# ADC.net
KiCad netlist of a schematic drawn in Altium Designer
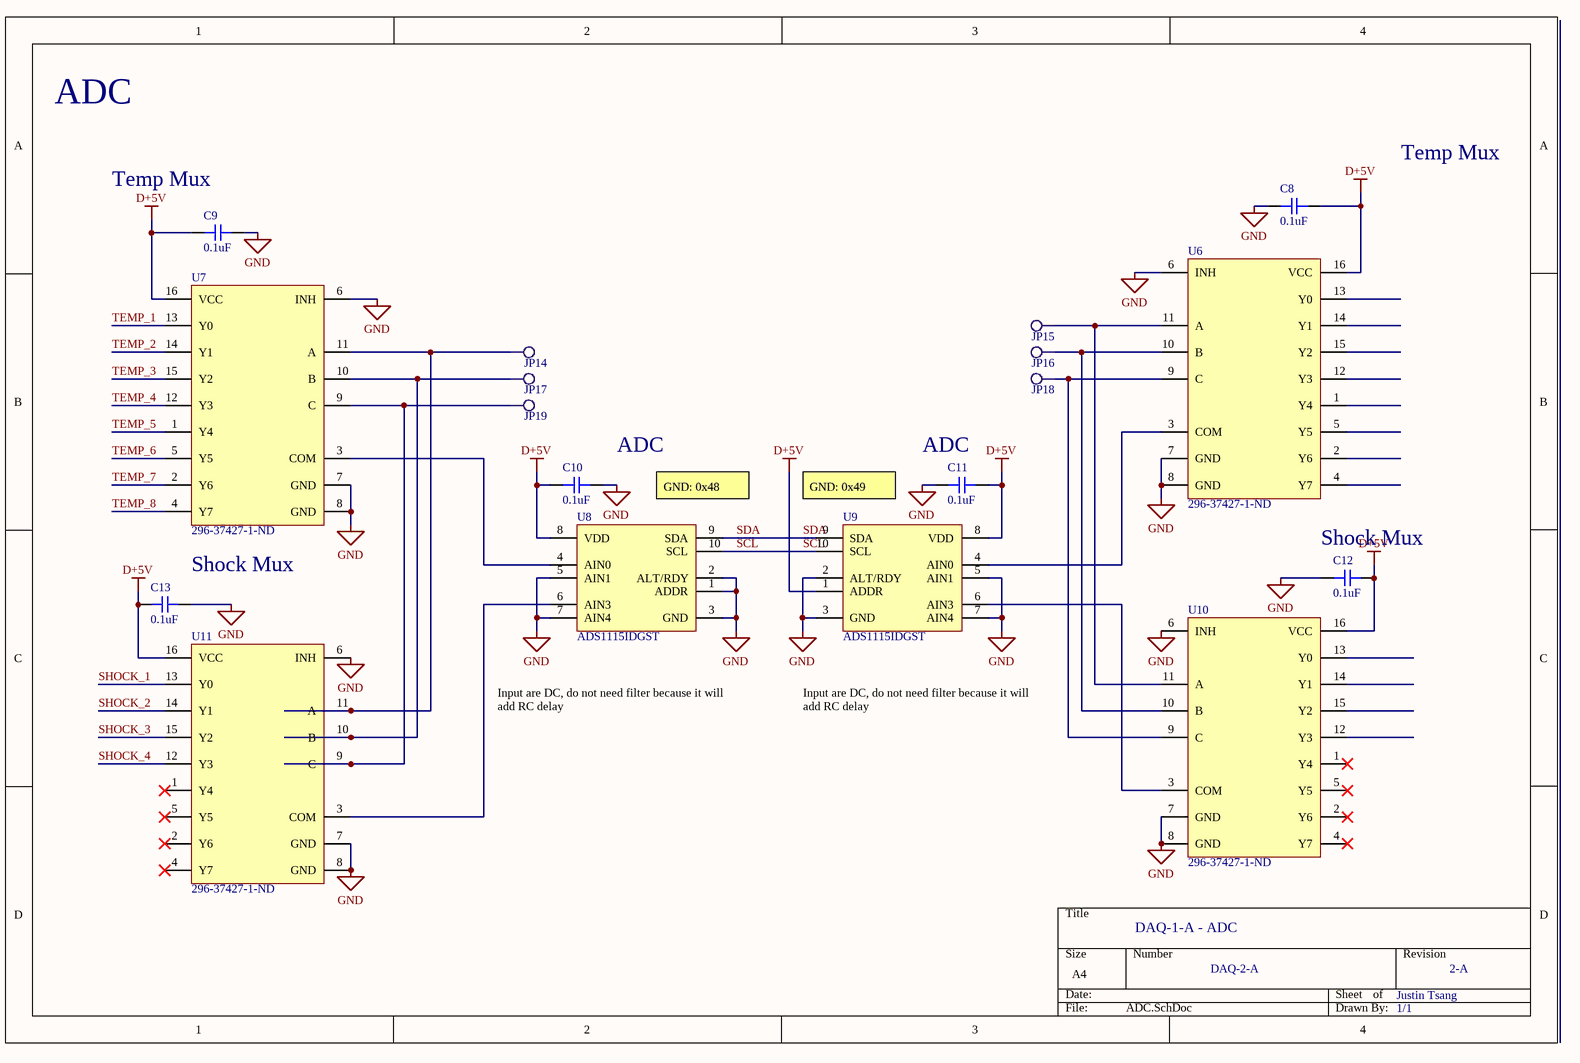
[diagram p0: ADC.SchDoc]

(export (version "E")
  (design (tool "Eeschema 10.0.6"))
  (components
    (comp (ref "C8")
      (value "0.1uF")
      (footprint "CAP-0603")
      (description "CAP CER 0.1UF 16V X7R 0603")
      (fields
        (field (name "MANUFACTURER") "KEMET")
        (field (name "MANUFACTURER PART NUMBER") "C0603C104M4RACTU")
      )
      (libsource (lib "Capacitors") (part "0603-0.1uF-16V"))
    )
    (comp (ref "C9")
      (value "0.1uF")
      (footprint "CAP-0603")
      (description "CAP CER 0.1UF 16V X7R 0603")
      (fields
        (field (name "MANUFACTURER") "KEMET")
        (field (name "MANUFACTURER PART NUMBER") "C0603C104M4RACTU")
      )
      (libsource (lib "Capacitors") (part "0603-0.1uF-16V"))
    )
    (comp (ref "C10")
      (value "0.1uF")
      (footprint "CAP-0603")
      (description "CAP CER 0.1UF 16V X7R 0603")
      (fields
        (field (name "MANUFACTURER") "KEMET")
        (field (name "MANUFACTURER PART NUMBER") "C0603C104M4RACTU")
      )
      (libsource (lib "Capacitors") (part "0603-0.1uF-16V"))
    )
    (comp (ref "C11")
      (value "0.1uF")
      (footprint "CAP-0603")
      (description "CAP CER 0.1UF 16V X7R 0603")
      (fields
        (field (name "MANUFACTURER") "KEMET")
        (field (name "MANUFACTURER PART NUMBER") "C0603C104M4RACTU")
      )
      (libsource (lib "Capacitors") (part "0603-0.1uF-16V"))
    )
    (comp (ref "C12")
      (value "0.1uF")
      (footprint "CAP-0603")
      (description "CAP CER 0.1UF 16V X7R 0603")
      (fields
        (field (name "MANUFACTURER") "KEMET")
        (field (name "MANUFACTURER PART NUMBER") "C0603C104M4RACTU")
      )
      (libsource (lib "Capacitors") (part "0603-0.1uF-16V"))
    )
    (comp (ref "C13")
      (value "0.1uF")
      (footprint "CAP-0603")
      (description "CAP CER 0.1UF 16V X7R 0603")
      (fields
        (field (name "MANUFACTURER") "KEMET")
        (field (name "MANUFACTURER PART NUMBER") "C0603C104M4RACTU")
      )
      (libsource (lib "Capacitors") (part "0603-0.1uF-16V"))
    )
    (comp (ref "JP14")
      (value "Testpoint2")
      (footprint "TP2")
      (description "Single layer pad TP")
      (libsource (lib "Misc") (part "Testpoint2"))
    )
    (comp (ref "JP15")
      (value "Testpoint2")
      (footprint "TP2")
      (description "Single layer pad TP")
      (libsource (lib "Misc") (part "Testpoint2"))
    )
    (comp (ref "JP16")
      (value "Testpoint2")
      (footprint "TP2")
      (description "Single layer pad TP")
      (libsource (lib "Misc") (part "Testpoint2"))
    )
    (comp (ref "JP17")
      (value "Testpoint2")
      (footprint "TP2")
      (description "Single layer pad TP")
      (libsource (lib "Misc") (part "Testpoint2"))
    )
    (comp (ref "JP18")
      (value "Testpoint2")
      (footprint "TP2")
      (description "Single layer pad TP")
      (libsource (lib "Misc") (part "Testpoint2"))
    )
    (comp (ref "JP19")
      (value "Testpoint2")
      (footprint "TP2")
      (description "Single layer pad TP")
      (libsource (lib "Misc") (part "Testpoint2"))
    )
    (comp (ref "U6")
      (value "296-37427-1-ND")
      (footprint "16-SOIC")
      (description "IC MUX/DEMUX 8X1 16SOIC")
      (fields
        (field (name "MANUFACTURER") "Texas Instruments")
        (field (name "MANUFACTURER PART NUMBER") "SN74LV4051ATDWRQ1")
      )
      (libsource (lib "ICs") (part "MUX-SN74LV4051ATDWRQ1"))
    )
    (comp (ref "U7")
      (value "296-37427-1-ND")
      (footprint "16-SOIC")
      (description "IC MUX/DEMUX 8X1 16SOIC")
      (fields
        (field (name "MANUFACTURER") "Texas Instruments")
        (field (name "MANUFACTURER PART NUMBER") "SN74LV4051ATDWRQ1")
      )
      (libsource (lib "") (part "MUX-SN74LV4051ATDWRQ1_1"))
    )
    (comp (ref "U8")
      (value "ADS1115IDGST")
      (footprint "VSSOP50P310X310-10P")
      (fields (field (name "MANUFACTURER") "Texas Instruments"))
      (libsource (lib "") (part "IC_ADS1115_1"))
    )
    (comp (ref "U9")
      (value "ADS1115IDGST")
      (footprint "VSSOP50P310X310-10P")
      (fields (field (name "MANUFACTURER") "Texas Instruments"))
      (libsource (lib "New_Parts") (part "IC_ADS1115"))
    )
    (comp (ref "U10")
      (value "296-37427-1-ND")
      (footprint "16-SOIC")
      (description "IC MUX/DEMUX 8X1 16SOIC")
      (fields
        (field (name "MANUFACTURER") "Texas Instruments")
        (field (name "MANUFACTURER PART NUMBER") "SN74LV4051ATDWRQ1")
      )
      (libsource (lib "ICs") (part "MUX-SN74LV4051ATDWRQ1"))
    )
    (comp (ref "U11")
      (value "296-37427-1-ND")
      (footprint "16-SOIC")
      (description "IC MUX/DEMUX 8X1 16SOIC")
      (fields
        (field (name "MANUFACTURER") "Texas Instruments")
        (field (name "MANUFACTURER PART NUMBER") "SN74LV4051ATDWRQ1")
      )
      (libsource (lib "") (part "MUX-SN74LV4051ATDWRQ1_1"))
    )
  )
  (nets
    (net (code "1") (name "/SCL") (class "Default")
      (node (ref "U8") (pin "10") (pinfunction "SCL_10") (pintype "passive"))
      (node (ref "U9") (pin "10") (pinfunction "SCL_10") (pintype "passive"))
    )
    (net (code "2") (name "/SDA") (class "Default")
      (node (ref "U8") (pin "9") (pinfunction "SDA_9") (pintype "passive"))
      (node (ref "U9") (pin "9") (pinfunction "SDA_9") (pintype "passive"))
    )
    (net (code "3") (name "/SHOCK_1") (class "Default")
      (node (ref "U11") (pin "13") (pinfunction "Y0_13") (pintype "passive"))
    )
    (net (code "4") (name "/SHOCK_2") (class "Default")
      (node (ref "U11") (pin "14") (pinfunction "Y1_14") (pintype "passive"))
    )
    (net (code "5") (name "/SHOCK_3") (class "Default")
      (node (ref "U11") (pin "15") (pinfunction "Y2_15") (pintype "passive"))
    )
    (net (code "6") (name "/SHOCK_4") (class "Default")
      (node (ref "U11") (pin "12") (pinfunction "Y3_12") (pintype "passive"))
    )
    (net (code "7") (name "/TEMP_1") (class "Default")
      (node (ref "U7") (pin "13") (pinfunction "Y0_13") (pintype "passive"))
    )
    (net (code "8") (name "/TEMP_2") (class "Default")
      (node (ref "U7") (pin "14") (pinfunction "Y1_14") (pintype "passive"))
    )
    (net (code "9") (name "/TEMP_3") (class "Default")
      (node (ref "U7") (pin "15") (pinfunction "Y2_15") (pintype "passive"))
    )
    (net (code "10") (name "/TEMP_4") (class "Default")
      (node (ref "U7") (pin "12") (pinfunction "Y3_12") (pintype "passive"))
    )
    (net (code "11") (name "/TEMP_5") (class "Default")
      (node (ref "U7") (pin "1") (pinfunction "Y4_1") (pintype "passive"))
    )
    (net (code "12") (name "/TEMP_6") (class "Default")
      (node (ref "U7") (pin "5") (pinfunction "Y5_5") (pintype "passive"))
    )
    (net (code "13") (name "/TEMP_7") (class "Default")
      (node (ref "U7") (pin "2") (pinfunction "Y6_2") (pintype "passive"))
    )
    (net (code "14") (name "/TEMP_8") (class "Default")
      (node (ref "U7") (pin "4") (pinfunction "Y7_4") (pintype "passive"))
    )
    (net (code "15") (name "D+5V") (class "Default")
      (node (ref "C10") (pin "2") (pinfunction "2_2") (pintype "passive"))
      (node (ref "C11") (pin "2") (pinfunction "2_2") (pintype "passive"))
      (node (ref "C12") (pin "2") (pinfunction "2_2") (pintype "passive"))
      (node (ref "C13") (pin "2") (pinfunction "2_2") (pintype "passive"))
      (node (ref "C8") (pin "2") (pinfunction "2_2") (pintype "passive"))
      (node (ref "C9") (pin "2") (pinfunction "2_2") (pintype "passive"))
      (node (ref "U10") (pin "16") (pinfunction "VCC_16") (pintype "passive"))
      (node (ref "U11") (pin "16") (pinfunction "VCC_16") (pintype "passive"))
      (node (ref "U6") (pin "16") (pinfunction "VCC_16") (pintype "passive"))
      (node (ref "U7") (pin "16") (pinfunction "VCC_16") (pintype "passive"))
      (node (ref "U8") (pin "8") (pinfunction "VDD_8") (pintype "passive"))
      (node (ref "U9") (pin "1") (pinfunction "ADDR_1") (pintype "passive"))
      (node (ref "U9") (pin "8") (pinfunction "VDD_8") (pintype "passive"))
    )
    (net (code "16") (name "GND") (class "Default")
      (node (ref "C10") (pin "1") (pinfunction "1_1") (pintype "passive"))
      (node (ref "C11") (pin "1") (pinfunction "1_1") (pintype "passive"))
      (node (ref "C12") (pin "1") (pinfunction "1_1") (pintype "passive"))
      (node (ref "C13") (pin "1") (pinfunction "1_1") (pintype "passive"))
      (node (ref "C8") (pin "1") (pinfunction "1_1") (pintype "passive"))
      (node (ref "C9") (pin "1") (pinfunction "1_1") (pintype "passive"))
      (node (ref "U10") (pin "6") (pinfunction "INH_6") (pintype "passive"))
      (node (ref "U10") (pin "7") (pinfunction "GND_7") (pintype "passive"))
      (node (ref "U10") (pin "8") (pinfunction "GND_8") (pintype "passive"))
      (node (ref "U11") (pin "6") (pinfunction "INH_6") (pintype "passive"))
      (node (ref "U11") (pin "7") (pinfunction "GND_7") (pintype "passive"))
      (node (ref "U11") (pin "8") (pinfunction "GND_8") (pintype "passive"))
      (node (ref "U6") (pin "6") (pinfunction "INH_6") (pintype "passive"))
      (node (ref "U6") (pin "7") (pinfunction "GND_7") (pintype "passive"))
      (node (ref "U6") (pin "8") (pinfunction "GND_8") (pintype "passive"))
      (node (ref "U7") (pin "6") (pinfunction "INH_6") (pintype "passive"))
      (node (ref "U7") (pin "7") (pinfunction "GND_7") (pintype "passive"))
      (node (ref "U7") (pin "8") (pinfunction "GND_8") (pintype "passive"))
      (node (ref "U8") (pin "1") (pinfunction "ADDR_1") (pintype "passive"))
      (node (ref "U8") (pin "2") (pinfunction "ALT/RDY_2") (pintype "passive"))
      (node (ref "U8") (pin "3") (pinfunction "GND_3") (pintype "passive"))
      (node (ref "U8") (pin "5") (pinfunction "AIN1_5") (pintype "passive"))
      (node (ref "U8") (pin "7") (pinfunction "AIN4_7") (pintype "passive"))
      (node (ref "U9") (pin "2") (pinfunction "ALT/RDY_2") (pintype "passive"))
      (node (ref "U9") (pin "3") (pinfunction "GND_3") (pintype "passive"))
      (node (ref "U9") (pin "5") (pinfunction "AIN1_5") (pintype "passive"))
      (node (ref "U9") (pin "7") (pinfunction "AIN4_7") (pintype "passive"))
    )
    (net (code "17") (name "Net-(U6-COM)") (class "Default")
      (node (ref "U6") (pin "3") (pinfunction "COM_3") (pintype "passive"))
      (node (ref "U9") (pin "4") (pinfunction "AIN0_4") (pintype "passive"))
    )
    (net (code "18") (name "Net-(U7-COM)") (class "Default")
      (node (ref "U7") (pin "3") (pinfunction "COM_3") (pintype "passive"))
      (node (ref "U8") (pin "4") (pinfunction "AIN0_4") (pintype "passive"))
    )
    (net (code "19") (name "Net-(U10-A)") (class "Default")
      (node (ref "JP15") (pin "1") (pinfunction "1_1") (pintype "passive"))
      (node (ref "U10") (pin "11") (pinfunction "A_11") (pintype "passive"))
      (node (ref "U6") (pin "11") (pinfunction "A_11") (pintype "passive"))
    )
    (net (code "20") (name "Net-(U10-B)") (class "Default")
      (node (ref "JP16") (pin "1") (pinfunction "1_1") (pintype "passive"))
      (node (ref "U10") (pin "10") (pinfunction "B_10") (pintype "passive"))
      (node (ref "U6") (pin "10") (pinfunction "B_10") (pintype "passive"))
    )
    (net (code "21") (name "Net-(U10-C)") (class "Default")
      (node (ref "JP18") (pin "1") (pinfunction "1_1") (pintype "passive"))
      (node (ref "U10") (pin "9") (pinfunction "C_9") (pintype "passive"))
      (node (ref "U6") (pin "9") (pinfunction "C_9") (pintype "passive"))
    )
    (net (code "22") (name "Net-(U10-COM)") (class "Default")
      (node (ref "U10") (pin "3") (pinfunction "COM_3") (pintype "passive"))
      (node (ref "U9") (pin "6") (pinfunction "AIN3_6") (pintype "passive"))
    )
    (net (code "23") (name "Net-(U11-A)") (class "Default")
      (node (ref "JP14") (pin "1") (pinfunction "1_1") (pintype "passive"))
      (node (ref "U11") (pin "11") (pinfunction "A_11") (pintype "passive"))
      (node (ref "U7") (pin "11") (pinfunction "A_11") (pintype "passive"))
    )
    (net (code "24") (name "Net-(U11-B)") (class "Default")
      (node (ref "JP17") (pin "1") (pinfunction "1_1") (pintype "passive"))
      (node (ref "U11") (pin "10") (pinfunction "B_10") (pintype "passive"))
      (node (ref "U7") (pin "10") (pinfunction "B_10") (pintype "passive"))
    )
    (net (code "25") (name "Net-(U11-C)") (class "Default")
      (node (ref "JP19") (pin "1") (pinfunction "1_1") (pintype "passive"))
      (node (ref "U11") (pin "9") (pinfunction "C_9") (pintype "passive"))
      (node (ref "U7") (pin "9") (pinfunction "C_9") (pintype "passive"))
    )
    (net (code "26") (name "Net-(U11-COM)") (class "Default")
      (node (ref "U11") (pin "3") (pinfunction "COM_3") (pintype "passive"))
      (node (ref "U8") (pin "6") (pinfunction "AIN3_6") (pintype "passive"))
    )
    (net (code "27") (name "unconnected-(U6-Y0-Pad13)") (class "Default")
      (node (ref "U6") (pin "13") (pinfunction "Y0_13") (pintype "passive"))
    )
    (net (code "28") (name "unconnected-(U6-Y1-Pad14)") (class "Default")
      (node (ref "U6") (pin "14") (pinfunction "Y1_14") (pintype "passive"))
    )
    (net (code "29") (name "unconnected-(U6-Y2-Pad15)") (class "Default")
      (node (ref "U6") (pin "15") (pinfunction "Y2_15") (pintype "passive"))
    )
    (net (code "30") (name "unconnected-(U6-Y3-Pad12)") (class "Default")
      (node (ref "U6") (pin "12") (pinfunction "Y3_12") (pintype "passive"))
    )
    (net (code "31") (name "unconnected-(U6-Y4-Pad1)") (class "Default")
      (node (ref "U6") (pin "1") (pinfunction "Y4_1") (pintype "passive"))
    )
    (net (code "32") (name "unconnected-(U6-Y5-Pad5)") (class "Default")
      (node (ref "U6") (pin "5") (pinfunction "Y5_5") (pintype "passive"))
    )
    (net (code "33") (name "unconnected-(U6-Y6-Pad2)") (class "Default")
      (node (ref "U6") (pin "2") (pinfunction "Y6_2") (pintype "passive"))
    )
    (net (code "34") (name "unconnected-(U6-Y7-Pad4)") (class "Default")
      (node (ref "U6") (pin "4") (pinfunction "Y7_4") (pintype "passive"))
    )
    (net (code "35") (name "unconnected-(U10-Y0-Pad13)") (class "Default")
      (node (ref "U10") (pin "13") (pinfunction "Y0_13") (pintype "passive"))
    )
    (net (code "36") (name "unconnected-(U10-Y1-Pad14)") (class "Default")
      (node (ref "U10") (pin "14") (pinfunction "Y1_14") (pintype "passive"))
    )
    (net (code "37") (name "unconnected-(U10-Y2-Pad15)") (class "Default")
      (node (ref "U10") (pin "15") (pinfunction "Y2_15") (pintype "passive"))
    )
    (net (code "38") (name "unconnected-(U10-Y3-Pad12)") (class "Default")
      (node (ref "U10") (pin "12") (pinfunction "Y3_12") (pintype "passive"))
    )
    (net (code "39") (name "unconnected-(U10-Y4-Pad1)") (class "Default")
      (node (ref "U10") (pin "1") (pinfunction "Y4_1") (pintype "passive+no_connect"))
    )
    (net (code "40") (name "unconnected-(U10-Y5-Pad5)") (class "Default")
      (node (ref "U10") (pin "5") (pinfunction "Y5_5") (pintype "passive+no_connect"))
    )
    (net (code "41") (name "unconnected-(U10-Y6-Pad2)") (class "Default")
      (node (ref "U10") (pin "2") (pinfunction "Y6_2") (pintype "passive+no_connect"))
    )
    (net (code "42") (name "unconnected-(U10-Y7-Pad4)") (class "Default")
      (node (ref "U10") (pin "4") (pinfunction "Y7_4") (pintype "passive+no_connect"))
    )
    (net (code "43") (name "unconnected-(U11-Y4-Pad1)") (class "Default")
      (node (ref "U11") (pin "1") (pinfunction "Y4_1") (pintype "passive+no_connect"))
    )
    (net (code "44") (name "unconnected-(U11-Y5-Pad5)") (class "Default")
      (node (ref "U11") (pin "5") (pinfunction "Y5_5") (pintype "passive+no_connect"))
    )
    (net (code "45") (name "unconnected-(U11-Y6-Pad2)") (class "Default")
      (node (ref "U11") (pin "2") (pinfunction "Y6_2") (pintype "passive+no_connect"))
    )
    (net (code "46") (name "unconnected-(U11-Y7-Pad4)") (class "Default")
      (node (ref "U11") (pin "4") (pinfunction "Y7_4") (pintype "passive+no_connect"))
    )
  )
)
